# Pg12_USB_UART.net
KiCad netlist of a schematic drawn in Altium Designer
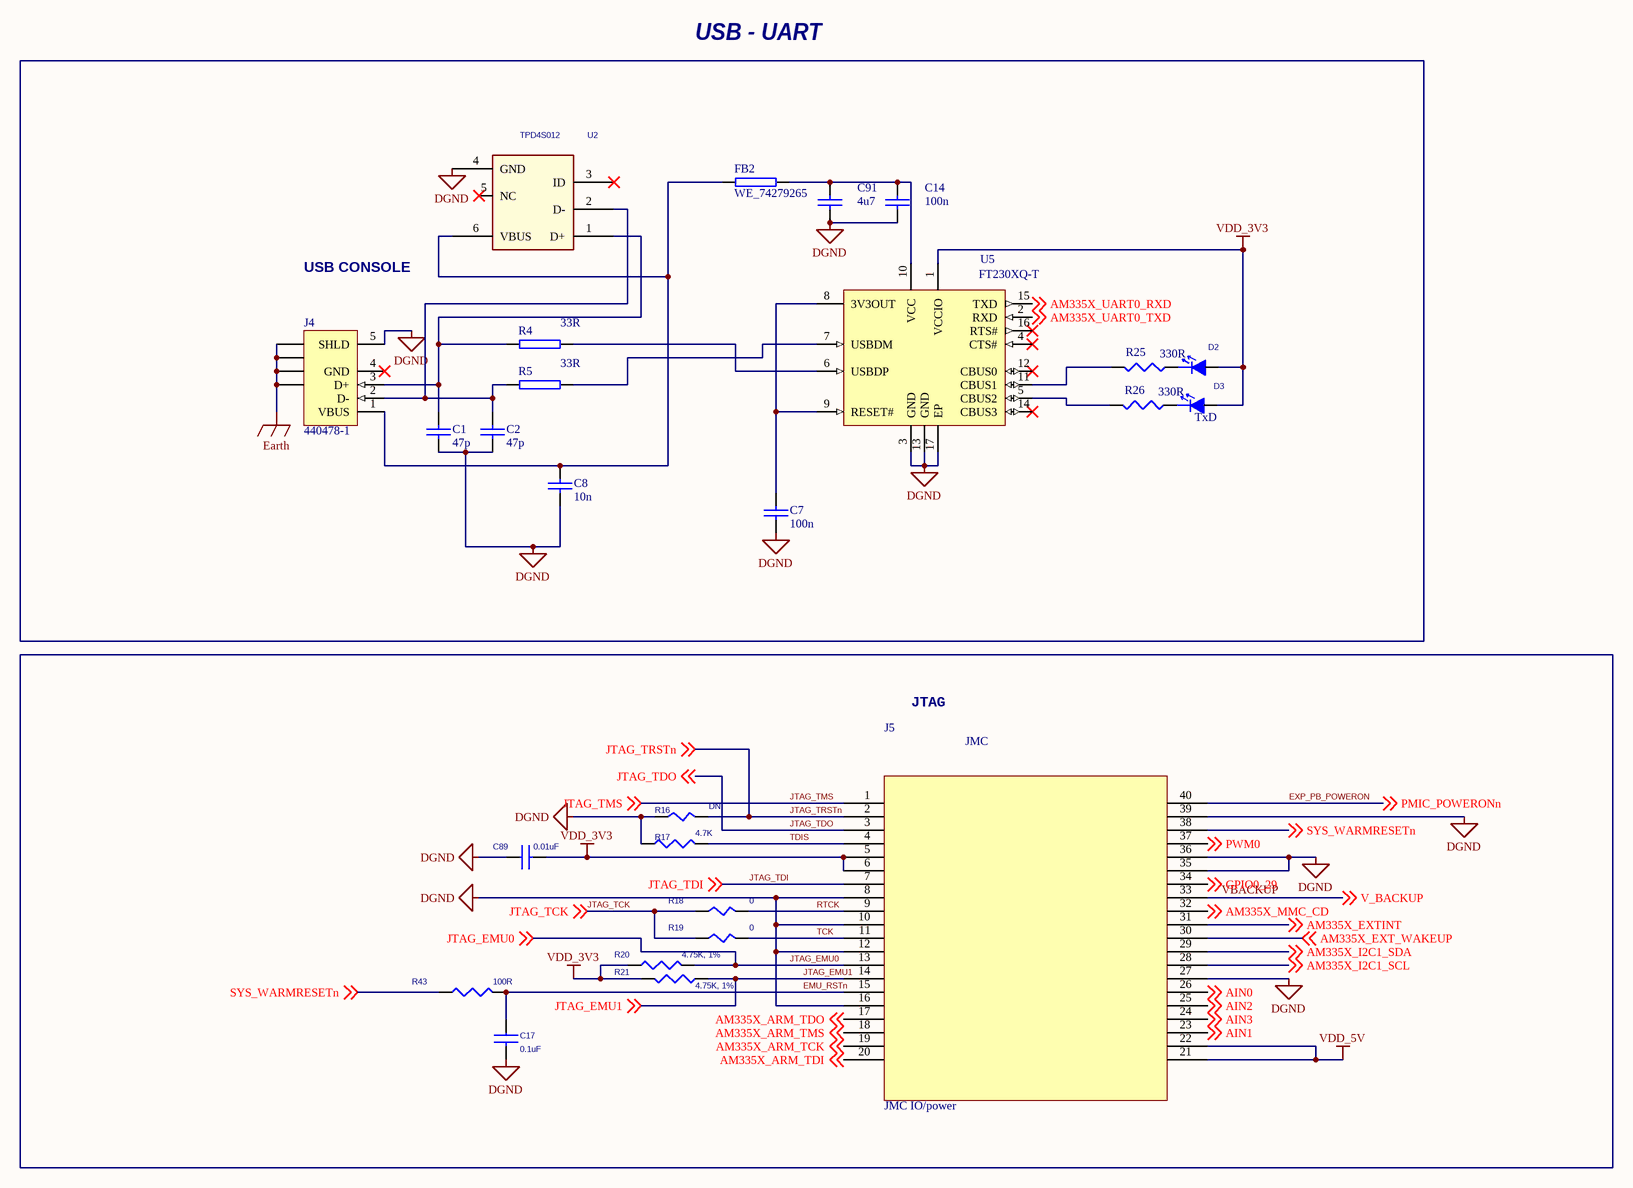
[diagram p0: Pg12_USB_UART.SchDoc]

(export (version "E")
  (design (tool "Eeschema 10.0.6"))
  (components
    (comp (ref "C1")
      (value "47p")
      (footprint "SM-7351-CAP-0402")
      (description "NON-POLARISED CAP")
      (libsource (lib "Fireflash_B") (part "CAP"))
    )
    (comp (ref "C2")
      (value "47p")
      (footprint "SM-7351-CAP-0402")
      (description "NON-POLARISED CAP")
      (libsource (lib "Fireflash_B") (part "CAP"))
    )
    (comp (ref "C7")
      (value "100n")
      (footprint "SM-7351-CAP-0402")
      (description "NON-POLARISED CAP")
      (libsource (lib "Fireflash_B") (part "CAP"))
    )
    (comp (ref "C8")
      (value "10n")
      (footprint "SM-7351-CAP-0402")
      (description "NON-POLARISED CAP")
      (libsource (lib "Fireflash_B") (part "CAP"))
    )
    (comp (ref "C14")
      (value "100n")
      (footprint "SM-7351-CAP-0402")
      (description "NON-POLARISED CAP")
      (libsource (lib "Fireflash_B") (part "CAP"))
    )
    (comp (ref "C17")
      (value "0.1uF")
      (footprint "SM-7351-CAP-0402")
      (fields (field (name "MFR") "Kemet") (field (name "TIINTPARTNUMBER") "1C0089"))
      (libsource (lib "*") (part "0.1uFCapacitor16V10%0402"))
    )
    (comp (ref "C89")
      (value "0.01uF")
      (footprint "SM-7351-CAP-0402")
      (fields (field (name "MFR") "Panasonic") (field (name "TIINTPARTNUMBER") "1C0012"))
      (libsource (lib "*") (part "0.01uFCapacitor16V10%0402_Dup1"))
    )
    (comp (ref "C91")
      (value "4u7")
      (footprint "0603")
      (description "NON-POLARISED CAP")
      (libsource (lib "Fireflash_B") (part "CAP"))
    )
    (comp (ref "D2")
      (value "Green LED")
      (footprint "0603")
      (fields (field (name "TIINTPARTNUMBER") "1F0008") (field (name "MFR") "Dialight"))
      (libsource (lib "ARMflash_mini") (part "LED_Green"))
    )
    (comp (ref "D3")
      (value "Green LED")
      (footprint "0603")
      (fields (field (name "TIINTPARTNUMBER") "1F0008") (field (name "MFR") "Dialight"))
      (libsource (lib "ARMflash_mini") (part "LED_Green"))
    )
    (comp (ref "FB2")
      (value "WE_74279265")
      (footprint "0603")
      (description "Wurth Eleckronik 0603 ferrite bead pn 74279265")
      (libsource (lib "Ibis4") (part "WE_74279265"))
    )
    (comp (ref "J4")
      (value "440478-1")
      (footprint "ARMflash_mini:440478")
      (description "USB 2.0, Right Angle, SMT, A Type, Receptacle, 5 Position, Black")
      (fields (field (name "PUBLISHER") "Altium Limited"))
      (libsource (lib "AMP Serial Bus USB") (part "440478-1"))
    )
    (comp (ref "J5")
      (value "JMC IO/power")
      (footprint "40 Pin Female")
      (description "JST JMC 40 pin connector")
      (libsource (lib "ARMFlash") (part "JMC 40-pin"))
    )
    (comp (ref "R4")
      (value "33R")
      (footprint "SM-7351-RES-0402")
      (description "RESISTOR")
      (libsource (lib "Fireflash_B") (part "RES"))
    )
    (comp (ref "R5")
      (value "33R")
      (footprint "SM-7351-RES-0402")
      (description "RESISTOR")
      (libsource (lib "Fireflash_B") (part "RES"))
    )
    (comp (ref "R16")
      (value "DNI")
      (footprint "SM-7351-RES-0402")
      (description "Resistor Zero ohm Jumper 0402")
      (fields (field (name "TIINTPARTNUMBER") "1R0098") (field (name "MFR") "Panasonic"))
      (libsource (lib "*") (part "ZeroOhmResistor1/16W0402_Dup4"))
    )
    (comp (ref "R17")
      (value "4.7K")
      (footprint "SM-7351-RES-0402")
      (fields
        (field (name "MFR") "Panasonic-ECG")
        (field (name "TIINTPARTNUMBER") "1R0250")
        (field (name "PART NUMBER") "RES_4.75K_1/16W_1%_0402")
      )
      (libsource (lib "*") (part "4.75KohmResistor1/16W1%0402"))
    )
    (comp (ref "R18")
      (value "0")
      (footprint "SM-7351-RES-0402")
      (description "Resistor Zero ohm Jumper 0402")
      (fields (field (name "TIINTPARTNUMBER") "1R0098") (field (name "MFR") "Panasonic"))
      (libsource (lib "*") (part "ZeroOhmResistor1/16W0402_Dup4"))
    )
    (comp (ref "R19")
      (value "0")
      (footprint "SM-7351-RES-0402")
      (description "Resistor Zero ohm Jumper 0402")
      (fields (field (name "TIINTPARTNUMBER") "1R0098") (field (name "MFR") "Panasonic"))
      (libsource (lib "*") (part "ZeroOhmResistor1/16W0402_Dup4"))
    )
    (comp (ref "R20")
      (value "4.75K, 1%")
      (footprint "SM-7351-RES-0402")
      (fields
        (field (name "MFR") "Panasonic-ECG")
        (field (name "TIINTPARTNUMBER") "1R0250")
        (field (name "PART NUMBER") "RES_4.75K_1/16W_1%_0402")
      )
      (libsource (lib "*") (part "4.75KohmResistor1/16W1%0402"))
    )
    (comp (ref "R21")
      (value "4.75K, 1%")
      (footprint "SM-7351-RES-0402")
      (fields
        (field (name "MFR") "Panasonic-ECG")
        (field (name "TIINTPARTNUMBER") "1R0250")
        (field (name "PART NUMBER") "RES_4.75K_1/16W_1%_0402")
      )
      (libsource (lib "*") (part "4.75KohmResistor1/16W1%0402"))
    )
    (comp (ref "R25")
      (value "330R")
      (footprint "SM-7351-RES-0402")
      (fields (field (name "MFR") "Stackpole Electronics") (field (name "TIINTPARTNUMBER") "1R0182"))
      (libsource (lib "ARMflash_mini") (part "1MOhmResistor1/16W0402"))
    )
    (comp (ref "R26")
      (value "330R")
      (footprint "SM-7351-RES-0402")
      (fields (field (name "MFR") "Stackpole Electronics") (field (name "TIINTPARTNUMBER") "1R0182"))
      (libsource (lib "ARMflash_mini") (part "1MOhmResistor1/16W0402"))
    )
    (comp (ref "R43")
      (value "100R")
      (footprint "SM-7351-RES-0402")
      (fields (field (name "TIINTPARTNUMBER") "1R0236") (field (name "MFR") "Stackpole Electronics"))
      (libsource (lib "*") (part "100ohm1/16W1%SMD0402"))
    )
    (comp (ref "U2")
      (value "TPD4S012")
      (footprint "U_6_DRY")
      (description "ESD 4channel USB Interface")
      (fields (field (name "MFR") "TI") (field (name "TIINTPARTNUMBER") "1A0233"))
      (libsource (lib "*") (part "TPD4S012"))
    )
    (comp (ref "U5")
      (value "FT230XQ-T")
      (footprint "MED_SOC:QFN-16_N")
      (fields (field (name "MANUFACTURER") "FTDI"))
      (libsource (lib "FTDI FT-X Series") (part "FT230XQ-T"))
    )
  )
  (nets
    (net (code "1") (name "/EMU_RSTn") (class "Default")
      (node (ref "C17") (pin "1") (pinfunction "1_1") (pintype "passive"))
      (node (ref "J5") (pin "15") (pintype "passive"))
      (node (ref "R43") (pin "1") (pinfunction "P1_1") (pintype "passive"))
    )
    (net (code "2") (name "/RTCK") (class "Default")
      (node (ref "J5") (pin "9") (pintype "passive"))
      (node (ref "R18") (pin "1") (pinfunction "P1_1") (pintype "passive"))
    )
    (net (code "3") (name "/TCK") (class "Default")
      (node (ref "J5") (pin "11") (pintype "passive"))
      (node (ref "R19") (pin "1") (pinfunction "P1_1") (pintype "passive"))
    )
    (net (code "4") (name "/TDIS") (class "Default")
      (node (ref "J5") (pin "4") (pintype "passive"))
      (node (ref "R17") (pin "2") (pinfunction "2_2") (pintype "passive"))
    )
    (net (code "5") (name "AIN0") (class "Default") (node (ref "J5") (pin "26") (pintype "passive")))
    (net (code "6") (name "AIN1") (class "Default") (node (ref "J5") (pin "23") (pintype "passive")))
    (net (code "7") (name "AIN2") (class "Default") (node (ref "J5") (pin "25") (pintype "passive")))
    (net (code "8") (name "AIN3") (class "Default") (node (ref "J5") (pin "24") (pintype "passive")))
    (net (code "9") (name "AM335X_ARM_TCK") (class "Default")
      (node (ref "J5") (pin "19") (pintype "passive"))
    )
    (net (code "10") (name "AM335X_ARM_TDI") (class "Default")
      (node (ref "J5") (pin "20") (pintype "passive"))
    )
    (net (code "11") (name "AM335X_ARM_TDO") (class "Default")
      (node (ref "J5") (pin "17") (pintype "passive"))
    )
    (net (code "12") (name "AM335X_ARM_TMS") (class "Default")
      (node (ref "J5") (pin "18") (pintype "passive"))
    )
    (net (code "13") (name "AM335X_EXTINT") (class "Default")
      (node (ref "J5") (pin "31") (pintype "passive"))
    )
    (net (code "14") (name "AM335X_EXT_WAKEUP") (class "Default")
      (node (ref "J5") (pin "30") (pintype "passive"))
    )
    (net (code "15") (name "AM335X_I2C1_SCL") (class "Default")
      (node (ref "J5") (pin "28") (pintype "passive"))
    )
    (net (code "16") (name "AM335X_I2C1_SDA") (class "Default")
      (node (ref "J5") (pin "29") (pintype "passive"))
    )
    (net (code "17") (name "AM335X_MMC_CD") (class "Default")
      (node (ref "J5") (pin "32") (pintype "passive"))
    )
    (net (code "18") (name "AM335X_UART0_RXD") (class "Default")
      (node (ref "U5") (pin "15") (pinfunction "TXD_15") (pintype "output"))
    )
    (net (code "19") (name "AM335X_UART0_TXD") (class "Default")
      (node (ref "U5") (pin "2") (pinfunction "RXD_2") (pintype "input"))
    )
    (net (code "20") (name "DGND") (class "Default")
      (node (ref "C1") (pin "2") (pintype "passive"))
      (node (ref "C14") (pin "2") (pintype "passive"))
      (node (ref "C17") (pin "2") (pinfunction "2_2") (pintype "passive"))
      (node (ref "C2") (pin "2") (pintype "passive"))
      (node (ref "C7") (pin "2") (pintype "passive"))
      (node (ref "C8") (pin "2") (pintype "passive"))
      (node (ref "C89") (pin "1") (pinfunction "1_1") (pintype "passive"))
      (node (ref "C91") (pin "2") (pintype "passive"))
      (node (ref "J4") (pin "5") (pinfunction "SHLD_5") (pintype "passive"))
      (node (ref "J5") (pin "10") (pintype "passive"))
      (node (ref "J5") (pin "12") (pintype "passive"))
      (node (ref "J5") (pin "16") (pintype "passive"))
      (node (ref "J5") (pin "27") (pintype "passive"))
      (node (ref "J5") (pin "35") (pintype "passive"))
      (node (ref "J5") (pin "36") (pintype "passive"))
      (node (ref "J5") (pin "39") (pintype "passive"))
      (node (ref "J5") (pin "8") (pintype "passive"))
      (node (ref "R16") (pin "2") (pinfunction "P2_2") (pintype "passive"))
      (node (ref "R17") (pin "1") (pinfunction "1_1") (pintype "passive"))
      (node (ref "U2") (pin "4") (pinfunction "GND_4") (pintype "power_in"))
      (node (ref "U5") (pin "13") (pinfunction "GND_13") (pintype "power_in"))
      (node (ref "U5") (pin "17") (pinfunction "EP_17") (pintype "power_in"))
      (node (ref "U5") (pin "3") (pinfunction "GND_3") (pintype "power_in"))
    )
    (net (code "21") (name "Earth") (class "Default")
      (node (ref "J4") (pin "6") (pinfunction "SHLD_6") (pintype "passive"))
      (node (ref "J4") (pin "7") (pinfunction "SHLD_7") (pintype "passive"))
      (node (ref "J4") (pin "8") (pinfunction "SHLD_8") (pintype "passive"))
      (node (ref "J4") (pin "9") (pinfunction "SHLD_9") (pintype "passive"))
    )
    (net (code "22") (name "GPIO0_29") (class "Default") (node (ref "J5") (pin "34") (pintype "passive")))
    (net (code "23") (name "JTAG_EMU0") (class "Default")
      (node (ref "J5") (pin "13") (pintype "passive"))
      (node (ref "R20") (pin "2") (pinfunction "2_2") (pintype "passive"))
    )
    (net (code "24") (name "JTAG_EMU1") (class "Default")
      (node (ref "J5") (pin "14") (pintype "passive"))
      (node (ref "R21") (pin "1") (pinfunction "1_1") (pintype "passive"))
    )
    (net (code "25") (name "JTAG_TCK") (class "Default")
      (node (ref "R18") (pin "2") (pinfunction "P2_2") (pintype "passive"))
      (node (ref "R19") (pin "2") (pinfunction "P2_2") (pintype "passive"))
    )
    (net (code "26") (name "JTAG_TDI") (class "Default") (node (ref "J5") (pin "7") (pintype "passive")))
    (net (code "27") (name "JTAG_TDO") (class "Default") (node (ref "J5") (pin "3") (pintype "passive")))
    (net (code "28") (name "JTAG_TMS") (class "Default") (node (ref "J5") (pin "1") (pintype "passive")))
    (net (code "29") (name "JTAG_TRSTn") (class "Default")
      (node (ref "J5") (pin "2") (pintype "passive"))
      (node (ref "R16") (pin "1") (pinfunction "P1_1") (pintype "passive"))
    )
    (net (code "30") (name "Net-(D2-Cathode)") (class "Default")
      (node (ref "D2") (pin "1") (pinfunction "Cathode_1") (pintype "passive"))
      (node (ref "R25") (pin "2") (pinfunction "P2_2") (pintype "passive"))
    )
    (net (code "31") (name "Net-(D3-Cathode)") (class "Default")
      (node (ref "D3") (pin "1") (pinfunction "Cathode_1") (pintype "passive"))
      (node (ref "R26") (pin "2") (pinfunction "P2_2") (pintype "passive"))
    )
    (net (code "32") (name "Net-(J4-D+)") (class "Default")
      (node (ref "C1") (pin "1") (pintype "passive"))
      (node (ref "J4") (pin "3") (pinfunction "D+_3") (pintype "input"))
      (node (ref "R4") (pin "2") (pintype "passive"))
      (node (ref "U2") (pin "1") (pinfunction "D+_1") (pintype "passive"))
    )
    (net (code "33") (name "Net-(J4-D-)") (class "Default")
      (node (ref "C2") (pin "1") (pintype "passive"))
      (node (ref "J4") (pin "2") (pinfunction "D-_2") (pintype "input"))
      (node (ref "R5") (pin "2") (pintype "passive"))
      (node (ref "U2") (pin "2") (pinfunction "D-_2") (pintype "passive"))
    )
    (net (code "34") (name "Net-(J4-VBUS)") (class "Default")
      (node (ref "C8") (pin "1") (pintype "passive"))
      (node (ref "FB2") (pin "1") (pintype "passive"))
      (node (ref "J4") (pin "1") (pinfunction "VBUS_1") (pintype "power_in"))
      (node (ref "U2") (pin "6") (pinfunction "VBUS_6") (pintype "power_in"))
    )
    (net (code "35") (name "Net-(R25-P1)") (class "Default")
      (node (ref "R25") (pin "1") (pinfunction "P1_1") (pintype "passive"))
      (node (ref "U5") (pin "11") (pinfunction "CBUS1_11") (pintype "bidirectional"))
    )
    (net (code "36") (name "Net-(R26-P1)") (class "Default")
      (node (ref "R26") (pin "1") (pinfunction "P1_1") (pintype "passive"))
      (node (ref "U5") (pin "5") (pinfunction "CBUS2_5") (pintype "bidirectional"))
    )
    (net (code "37") (name "Net-(U5-3V3OUT)") (class "Default")
      (node (ref "C7") (pin "1") (pintype "passive"))
      (node (ref "U5") (pin "8") (pinfunction "3V3OUT_8") (pintype "power_in"))
      (node (ref "U5") (pin "9") (pinfunction "RESET#_9") (pintype "input"))
    )
    (net (code "38") (name "Net-(U5-USBDM)") (class "Default")
      (node (ref "R5") (pin "1") (pintype "passive"))
      (node (ref "U5") (pin "7") (pinfunction "USBDM_7") (pintype "input"))
    )
    (net (code "39") (name "Net-(U5-USBDP)") (class "Default")
      (node (ref "R4") (pin "1") (pintype "passive"))
      (node (ref "U5") (pin "6") (pinfunction "USBDP_6") (pintype "input"))
    )
    (net (code "40") (name "Net-(U5-VCC)") (class "Default")
      (node (ref "C14") (pin "1") (pintype "passive"))
      (node (ref "C91") (pin "1") (pintype "passive"))
      (node (ref "FB2") (pin "2") (pintype "passive"))
      (node (ref "U5") (pin "10") (pinfunction "VCC_10") (pintype "power_in"))
    )
    (net (code "41") (name "PMIC_POWERONn") (class "Default")
      (node (ref "J5") (pin "40") (pintype "passive"))
    )
    (net (code "42") (name "PWM0") (class "Default") (node (ref "J5") (pin "37") (pintype "passive")))
    (net (code "43") (name "SYS_WARMRESETn") (class "Default")
      (node (ref "J5") (pin "38") (pintype "passive"))
      (node (ref "R43") (pin "2") (pinfunction "P2_2") (pintype "passive"))
    )
    (net (code "44") (name "VDD_3V3") (class "Default")
      (node (ref "C89") (pin "2") (pinfunction "2_2") (pintype "passive"))
      (node (ref "D2") (pin "2") (pinfunction "Anode_2") (pintype "passive"))
      (node (ref "D3") (pin "2") (pinfunction "Anode_2") (pintype "passive"))
      (node (ref "J5") (pin "5") (pintype "passive"))
      (node (ref "J5") (pin "6") (pintype "passive"))
      (node (ref "R20") (pin "1") (pinfunction "1_1") (pintype "passive"))
      (node (ref "R21") (pin "2") (pinfunction "2_2") (pintype "passive"))
      (node (ref "U5") (pin "1") (pinfunction "VCCIO_1") (pintype "power_in"))
    )
    (net (code "45") (name "VDD_5V") (class "Default")
      (node (ref "J5") (pin "21") (pintype "passive"))
      (node (ref "J5") (pin "22") (pintype "passive"))
    )
    (net (code "46") (name "V_BACKUP") (class "Default") (node (ref "J5") (pin "33") (pintype "passive")))
    (net (code "47") (name "unconnected-(J4-GND-Pad4)") (class "Default")
      (node (ref "J4") (pin "4") (pinfunction "GND_4") (pintype "power_in+no_connect"))
    )
    (net (code "48") (name "unconnected-(U2-ID-Pad3)") (class "Default")
      (node (ref "U2") (pin "3") (pinfunction "ID_3") (pintype "passive+no_connect"))
    )
    (net (code "49") (name "unconnected-(U2-NC-Pad5)") (class "Default")
      (node (ref "U2") (pin "5") (pinfunction "NC_5") (pintype "passive+no_connect"))
    )
    (net (code "50") (name "unconnected-(U5-CBUS0-Pad12)") (class "Default")
      (node (ref "U5") (pin "12") (pinfunction "CBUS0_12") (pintype "bidirectional+no_connect"))
    )
    (net (code "51") (name "unconnected-(U5-CBUS3-Pad14)") (class "Default")
      (node (ref "U5") (pin "14") (pinfunction "CBUS3_14") (pintype "bidirectional+no_connect"))
    )
    (net (code "52") (name "unconnected-(U5-CTS#-Pad4)") (class "Default")
      (node (ref "U5") (pin "4") (pinfunction "CTS#_4") (pintype "input+no_connect"))
    )
    (net (code "53") (name "unconnected-(U5-RTS#-Pad16)") (class "Default")
      (node (ref "U5") (pin "16") (pinfunction "RTS#_16") (pintype "output+no_connect"))
    )
  )
)
